# 358MU_IZNWBYTU20260630.net
KiCad netlist of a schematic drawn in Altium Designer
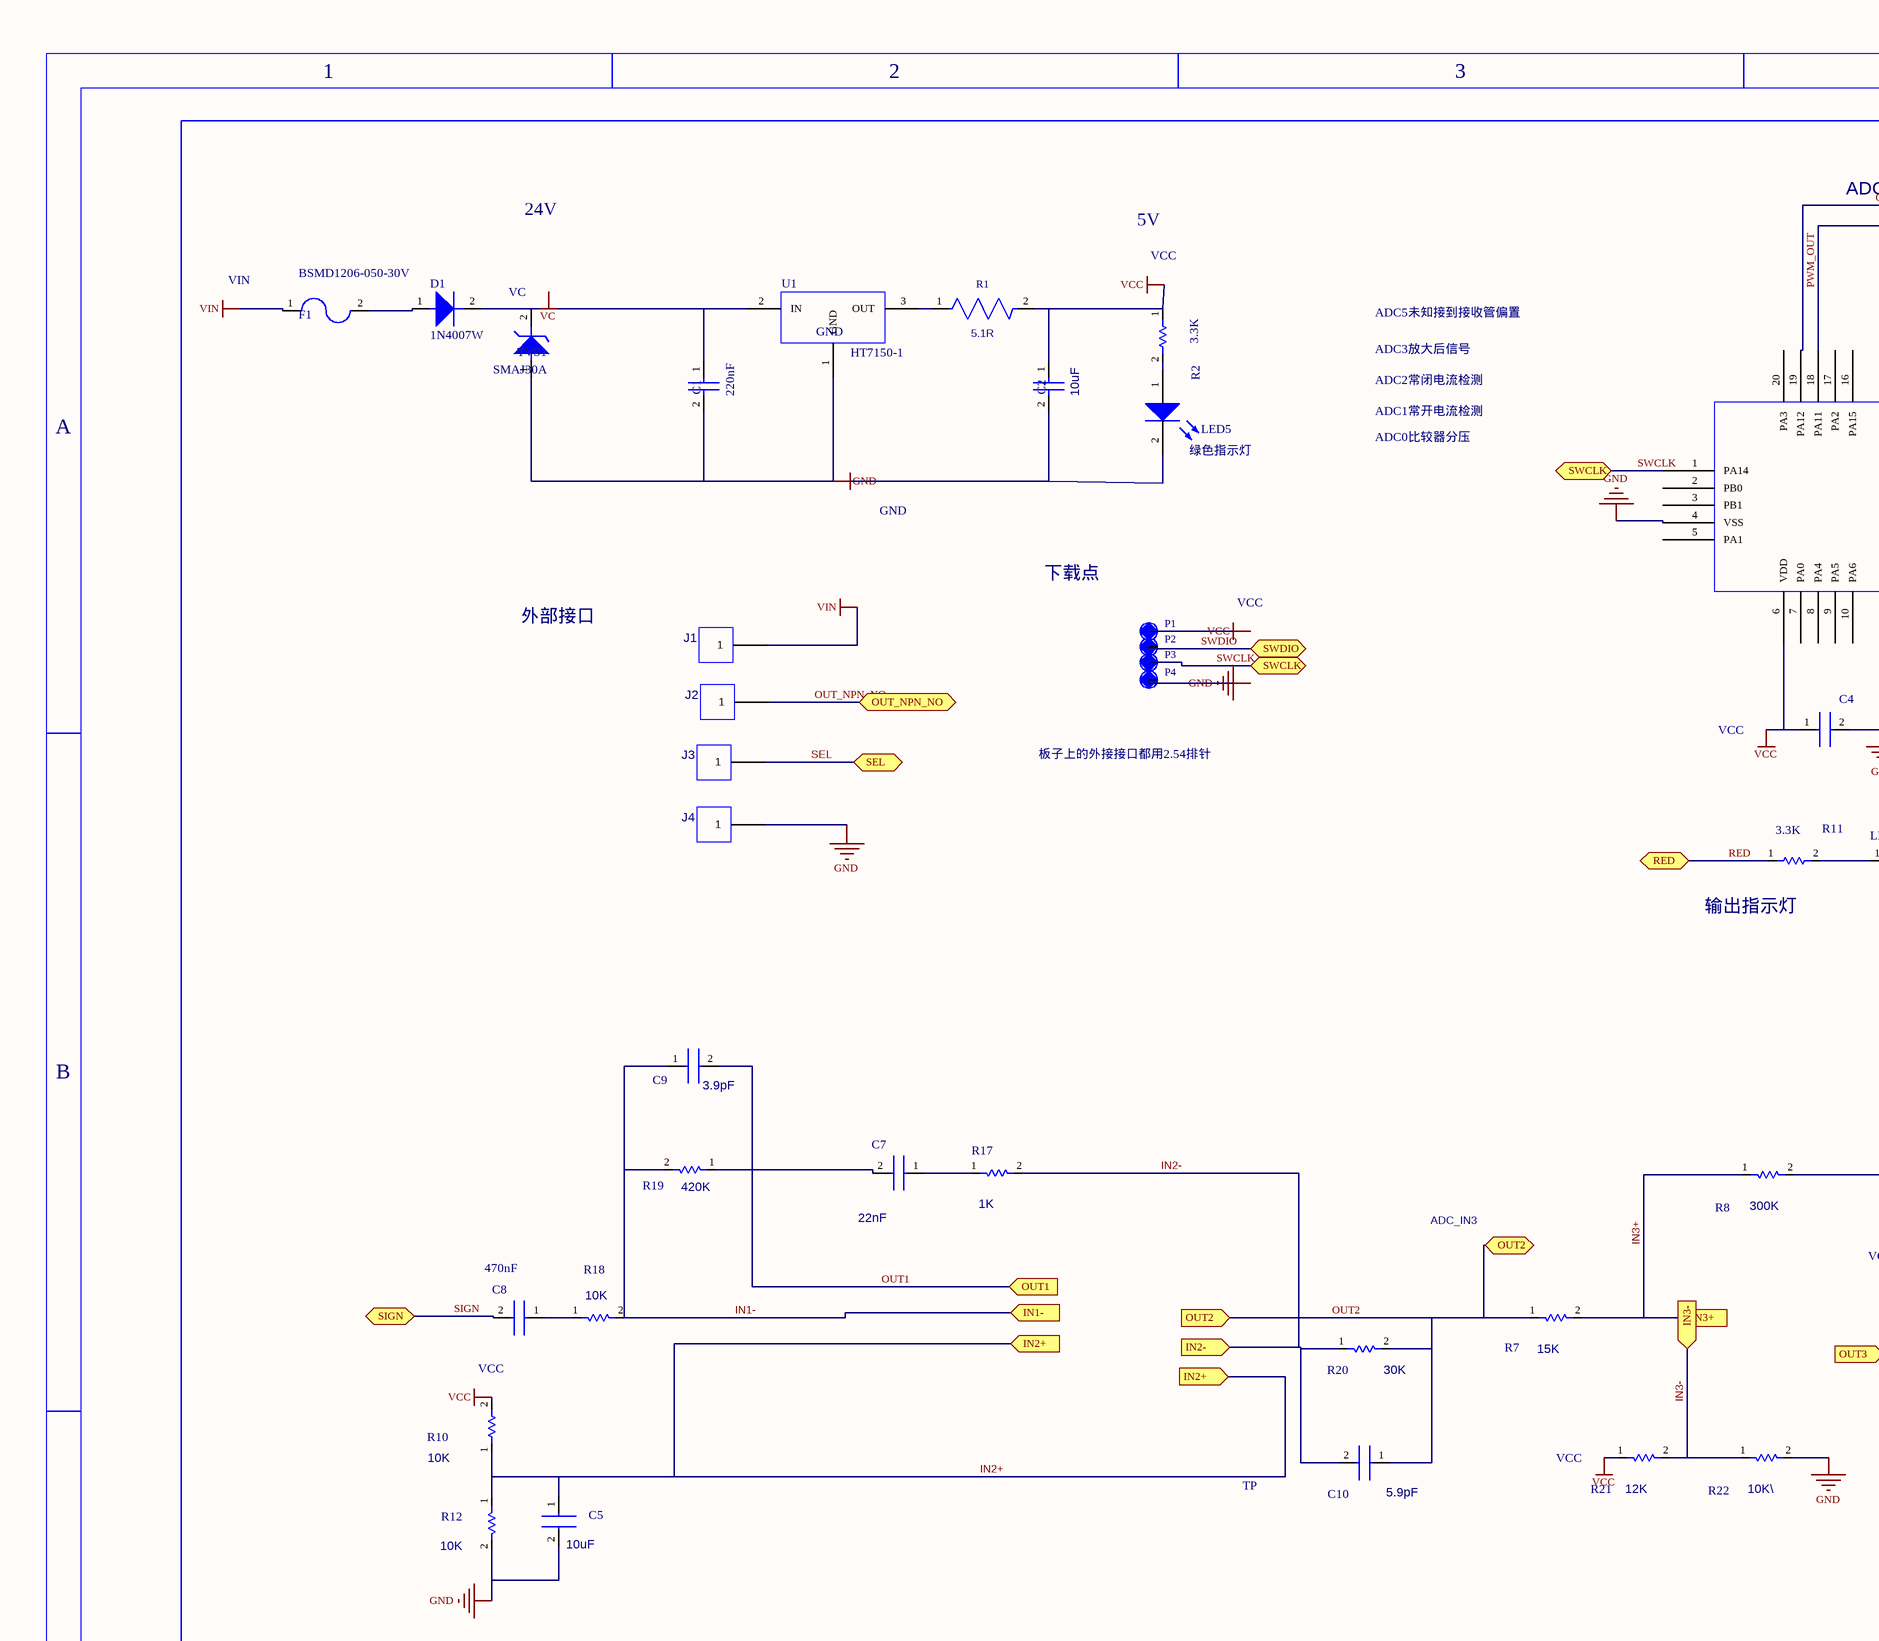
[diagram p0: 358MU&IZNWBYTU20260630.SchDoc, top left]
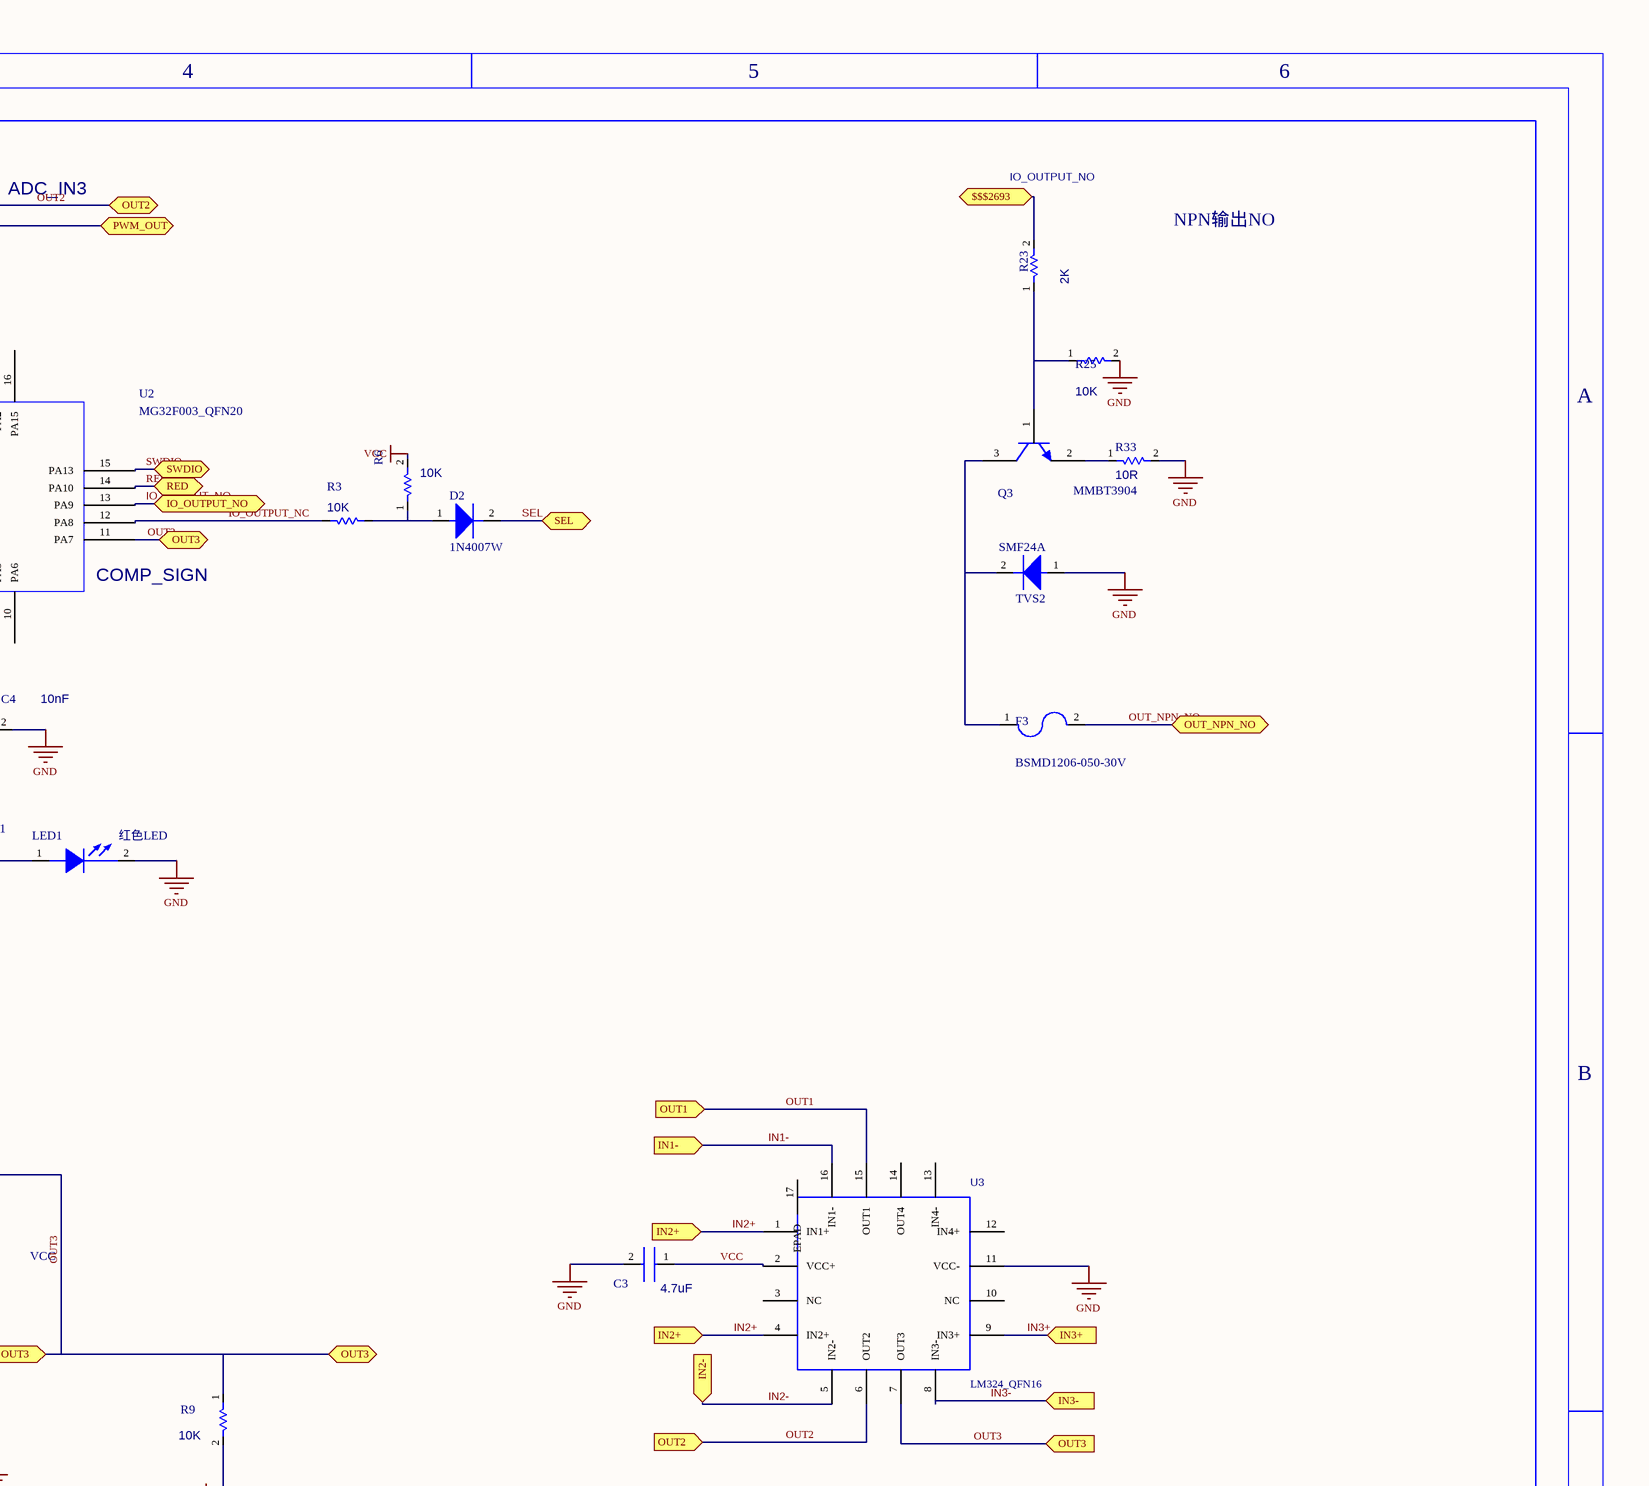
[diagram p1: 358MU&IZNWBYTU20260630.SchDoc, top right]
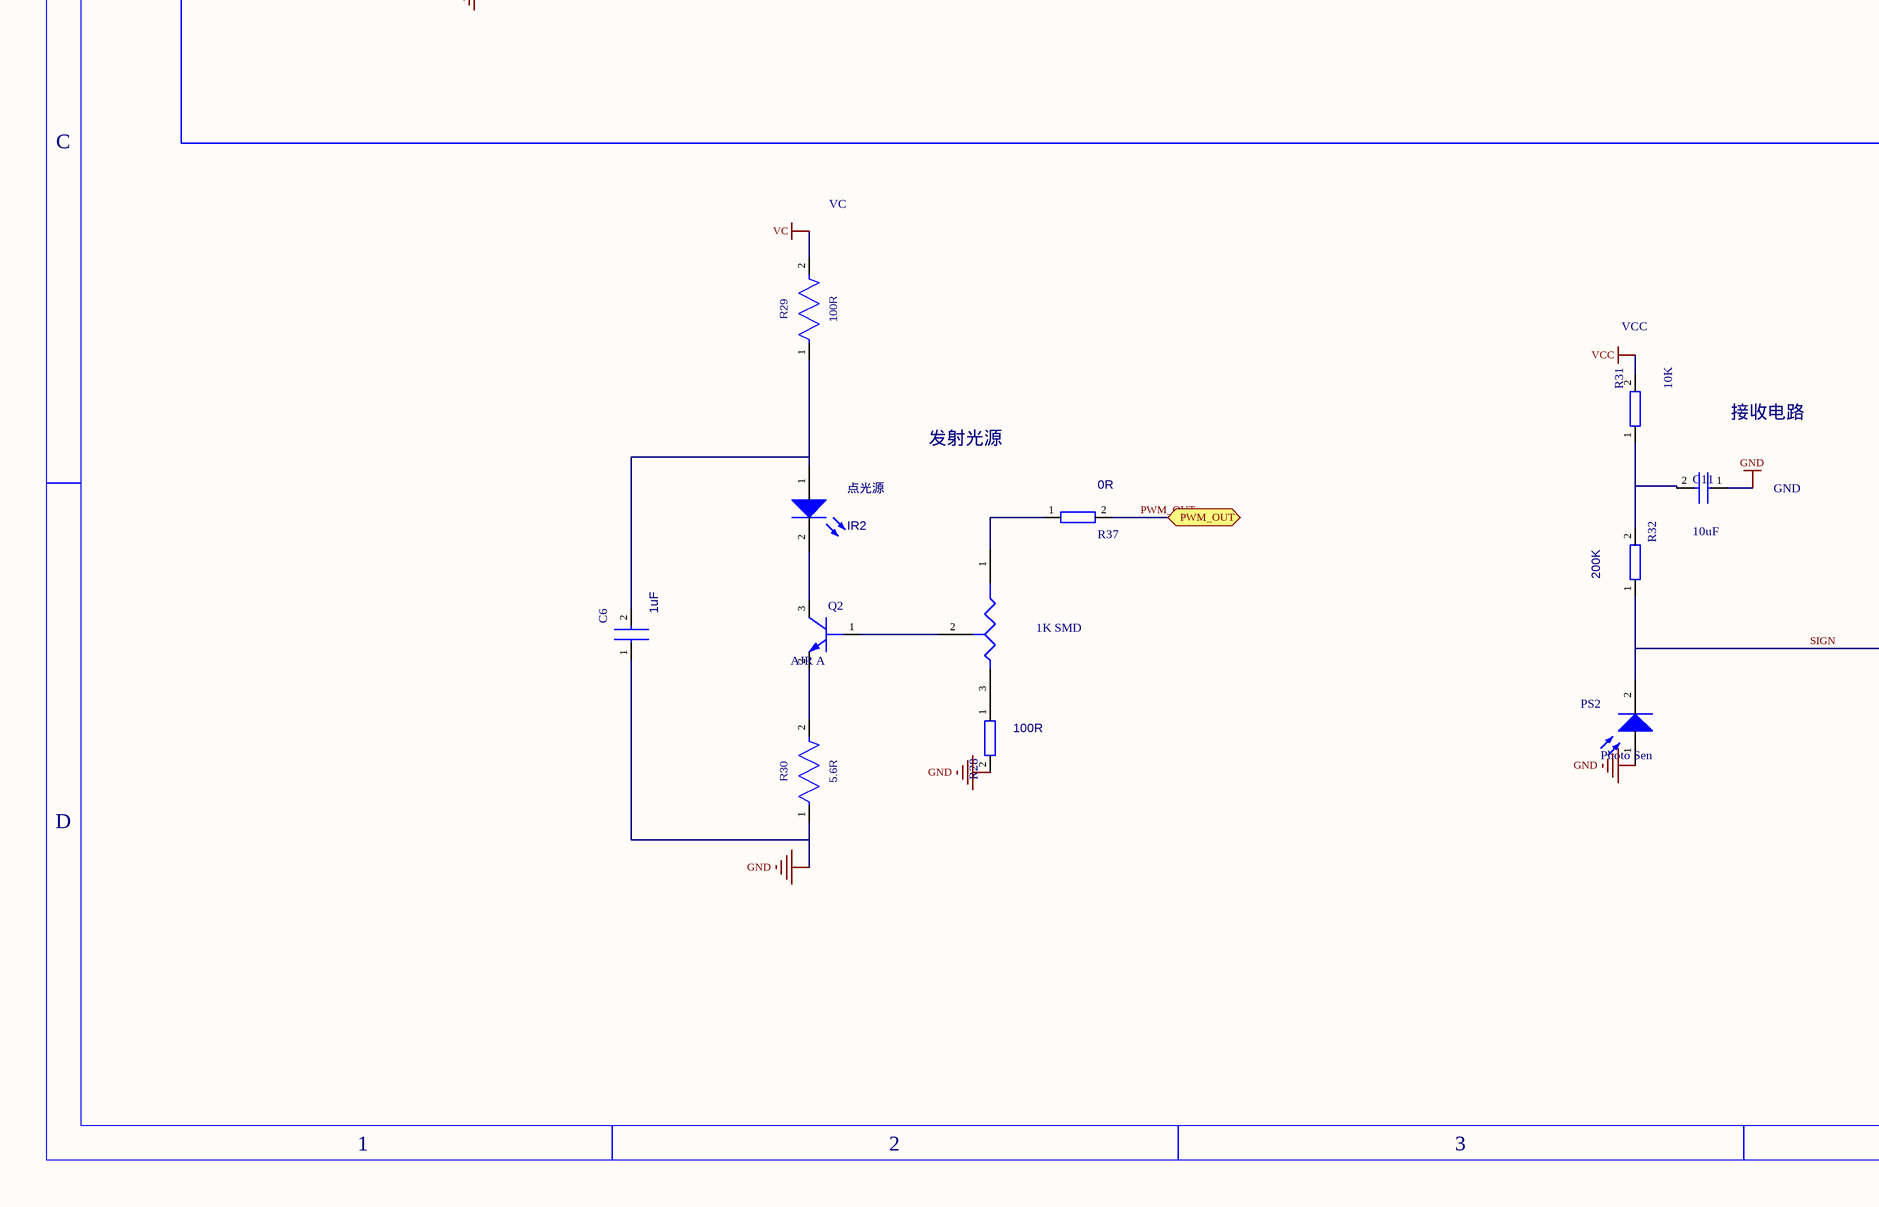
[diagram p2: 358MU&IZNWBYTU20260630.SchDoc, bottom left]
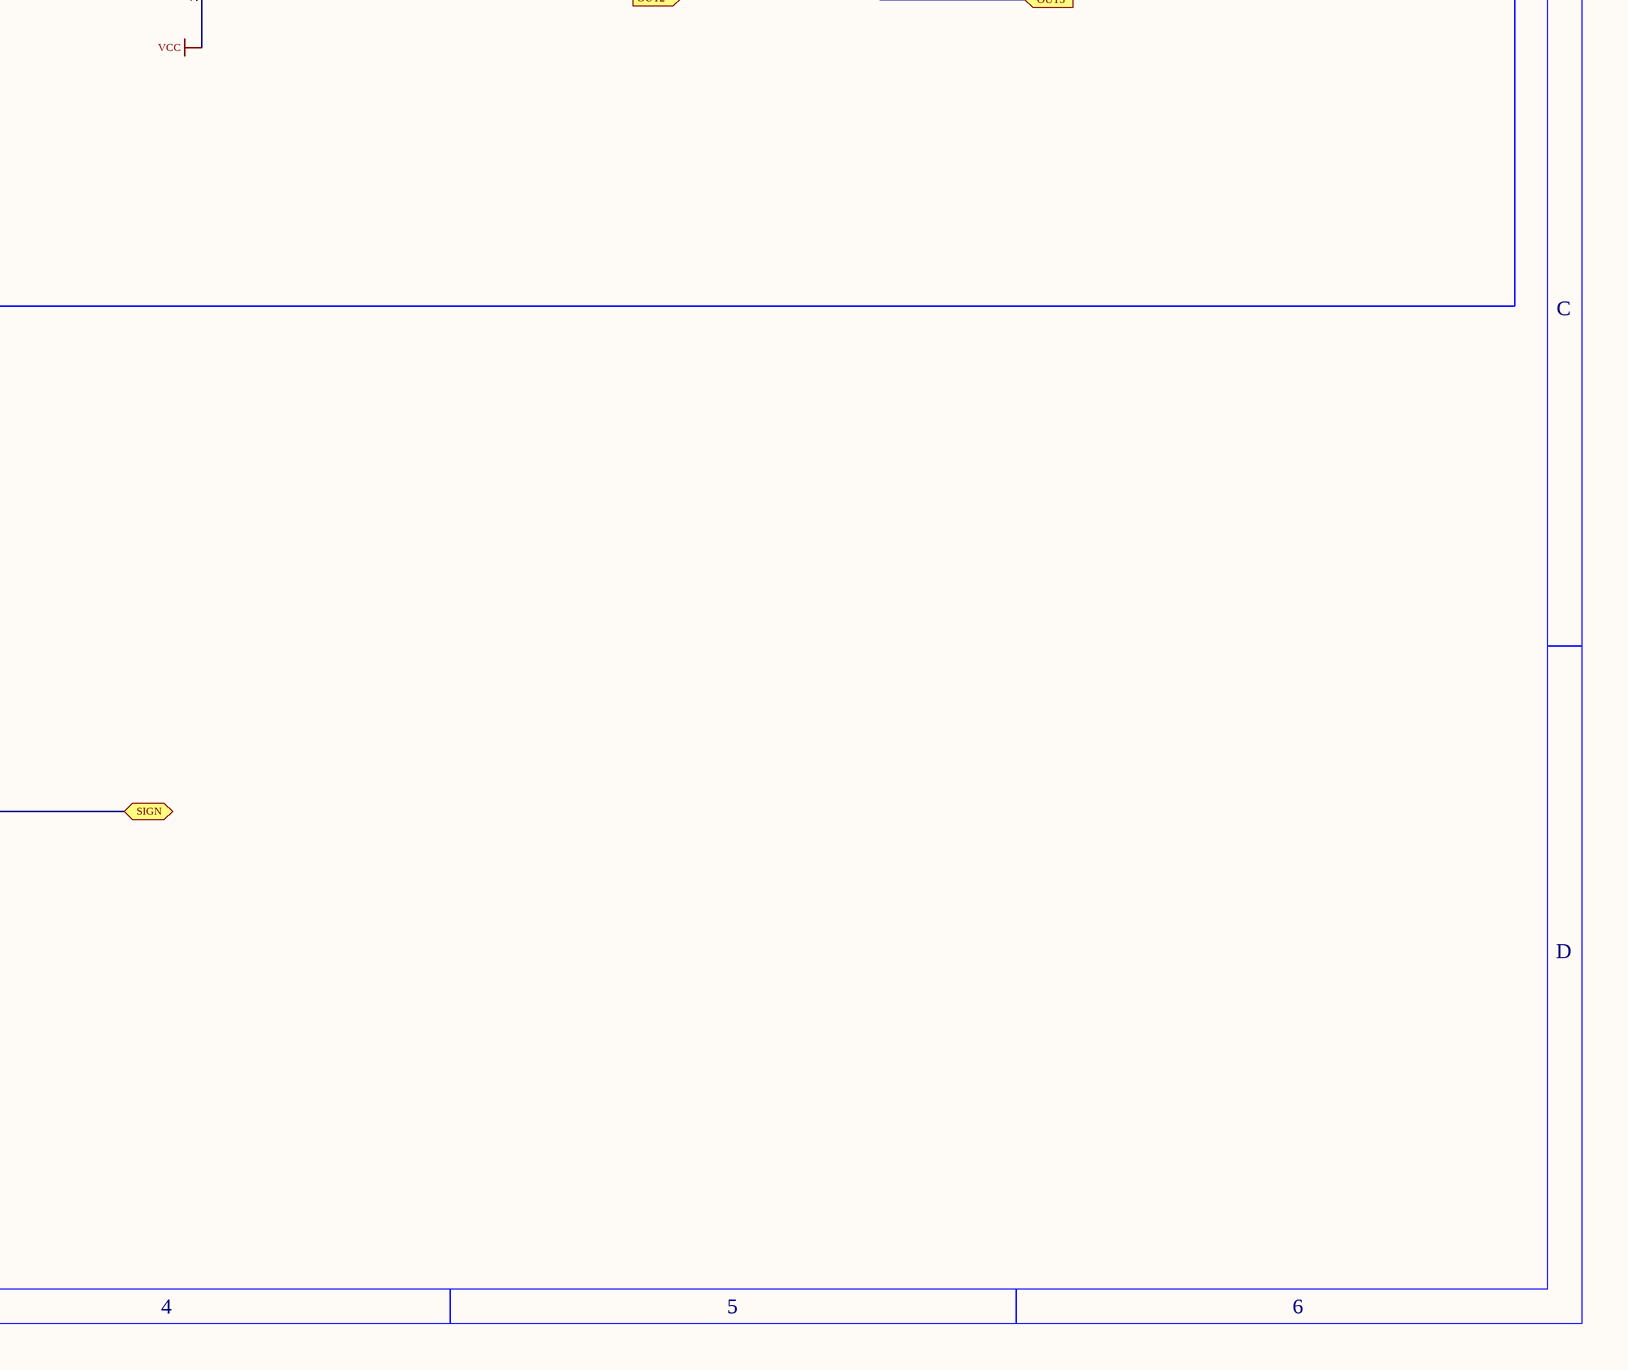
[diagram p3: 358MU&IZNWBYTU20260630.SchDoc, bottom right]

(export (version "E")
  (design (tool "Eeschema 10.0.6"))
  (components
    (comp (ref "C1")
      (value "CAP")
      (footprint "C0603")
      (description "陶瓷电容")
      (libsource (lib "*") (part "CAP"))
    )
    (comp (ref "C2")
      (value "CAP")
      (footprint "C0603")
      (description "陶瓷电容")
      (libsource (lib "*") (part "CAP"))
    )
    (comp (ref "C3") (value "CAP_2") (footprint "C0603") (libsource (lib "*") (part "CAP_2")))
    (comp (ref "C4")
      (value "CAP0402")
      (footprint "CC0402")
      (description "Capacitor")
      (libsource (lib "*") (part "CAP0402"))
    )
    (comp (ref "C5") (value "CAP_2") (footprint "C0603") (libsource (lib "*") (part "CAP_2")))
    (comp (ref "C6")
      (value "CAP0603")
      (footprint "0603C")
      (description "Capacitor")
      (libsource (lib "*") (part "CAP0603"))
    )
    (comp (ref "C7")
      (value "CAP0402")
      (footprint "CC0402")
      (description "Capacitor")
      (libsource (lib "*") (part "CAP0402"))
    )
    (comp (ref "C8")
      (value "CAP0402")
      (footprint "CC0402")
      (description "Capacitor")
      (libsource (lib "*") (part "CAP0402"))
    )
    (comp (ref "C9")
      (value "CAP0402")
      (footprint "CC0402")
      (description "Capacitor")
      (libsource (lib "*") (part "CAP0402"))
    )
    (comp (ref "C10")
      (value "CAP0402")
      (footprint "CC0402")
      (description "Capacitor")
      (libsource (lib "*") (part "CAP0402"))
    )
    (comp (ref "C11") (value "CAP_NP") (footprint "0603") (libsource (lib "*") (part "CAP_NP")))
    (comp (ref "D1")
      (value "DIODE")
      (footprint "WSOD-323")
      (description "Diode")
      (libsource (lib "*") (part "DIODE"))
    )
    (comp (ref "D2")
      (value "DIODE")
      (footprint "WSOD-323")
      (description "Diode")
      (libsource (lib "*") (part "DIODE"))
    )
    (comp (ref "F1")
      (value "FUSE")
      (footprint "0603")
      (description "Fuse")
      (libsource (lib "") (part "FUSE_1"))
    )
    (comp (ref "F3")
      (value "FUSE")
      (footprint "0603")
      (description "Fuse")
      (libsource (lib "*") (part "FUSE"))
    )
    (comp (ref "IR2")
      (value "LED0")
      (footprint "TXLED_SMD")
      (description "Typical INFRARED GaAs LED")
      (fields (field (name "PUBLISHER") "Altium Limited"))
      (libsource (lib "*") (part "LED0"))
    )
    (comp (ref "J1")
      (value "FPAD_3C")
      (footprint "FPAD_3C")
      (description "Connector")
      (libsource (lib "*") (part "FPAD_3C"))
    )
    (comp (ref "J2")
      (value "FPAD_3C")
      (footprint "FPAD_3C")
      (description "Connector")
      (libsource (lib "*") (part "FPAD_3C"))
    )
    (comp (ref "J3")
      (value "FPAD_3C")
      (footprint "FPAD_3C")
      (description "Connector")
      (libsource (lib "*") (part "FPAD_3C"))
    )
    (comp (ref "J4")
      (value "FPAD_3C")
      (footprint "FPAD_3C")
      (description "Connector")
      (libsource (lib "*") (part "FPAD_3C"))
    )
    (comp (ref "LED1") (value "LED") (footprint "LED0603") (libsource (lib "*") (part "LED")))
    (comp (ref "LED5")
      (value "LED2")
      (footprint "LED0603")
      (description "Typical RED, GREEN, YELLOW, AMBER GaAs LED")
      (fields (field (name "PUBLISHER") "Altium Limited"))
      (libsource (lib "*") (part "LED2"))
    )
    (comp (ref "P1")
      (value "TEST_POINTB+")
      (footprint "TEST-POINT_D1.0")
      (libsource (lib "*") (part "TEST_POINTB+"))
    )
    (comp (ref "P2")
      (value "TEST_POINTB+")
      (footprint "TEST-POINT_D1.0")
      (libsource (lib "*") (part "TEST_POINTB+"))
    )
    (comp (ref "P3")
      (value "TEST_POINTB+")
      (footprint "TEST-POINT_D1.0")
      (libsource (lib "*") (part "TEST_POINTB+"))
    )
    (comp (ref "P4")
      (value "TEST_POINTB+")
      (footprint "TEST-POINT_D1.0")
      (libsource (lib "*") (part "TEST_POINTB+"))
    )
    (comp (ref "PS2")
      (value "PHOTO_SEN")
      (footprint "RXLED_SMD")
      (description "Photosensitive Diode")
      (fields (field (name "PUBLISHER") "Altium Limited"))
      (libsource (lib "*") (part "PHOTO_SEN"))
    )
    (comp (ref "Q2") (value "Q2N2369_0") (footprint "SOT23/2") (libsource (lib "*") (part "Q2N2369_0")))
    (comp (ref "Q3")
      (value "NPNSOT23")
      (footprint "SOT23/2")
      (description "NPN Bipolar Transistor")
      (fields (field (name "PUBLISHER") "Altium Limited"))
      (libsource (lib "*") (part "NPNSOT23"))
    )
    (comp (ref "R1")
      (value "5.1R")
      (footprint "0603")
      (description "SURFACE MOUNT RESISTOR 0.031 X 0.061 INCHES, 1/10W")
      (fields (field (name "Comment") "RES0603"))
      (libsource (lib "*") (part "RES0603"))
    )
    (comp (ref "R2") (value "RAS0402") (footprint "R0402") (libsource (lib "*") (part "RAS0402")))
    (comp (ref "R3") (value "RAS0402") (footprint "R0402") (libsource (lib "") (part "RAS0402_1")))
    (comp (ref "R5")
      (value "1K SMD")
      (footprint "SMD")
      (description "Tapped Resistor")
      (fields (field (name "Comment") "ADJ_SMD") (field (name "PUBLISHER") "Altium Limited"))
      (libsource (lib "*") (part "ADJ_SMD"))
    )
    (comp (ref "R6") (value "RAS0402") (footprint "R0402") (libsource (lib "*") (part "RAS0402")))
    (comp (ref "R7") (value "RAS0402") (footprint "R0402") (libsource (lib "*") (part "RAS0402")))
    (comp (ref "R8") (value "RAS0402") (footprint "R0402") (libsource (lib "*") (part "RAS0402")))
    (comp (ref "R9") (value "RAS0402") (footprint "R0402") (libsource (lib "*") (part "RAS0402")))
    (comp (ref "R10") (value "RAS0402") (footprint "R0402") (libsource (lib "*") (part "RAS0402")))
    (comp (ref "R11") (value "RAS0402") (footprint "R0402") (libsource (lib "*") (part "RAS0402")))
    (comp (ref "R12") (value "RAS0402") (footprint "R0402") (libsource (lib "*") (part "RAS0402")))
    (comp (ref "R17") (value "RAS0402") (footprint "R0402") (libsource (lib "*") (part "RAS0402")))
    (comp (ref "R18") (value "RAS0402") (footprint "R0402") (libsource (lib "*") (part "RAS0402")))
    (comp (ref "R19") (value "RAS0402") (footprint "R0402") (libsource (lib "*") (part "RAS0402")))
    (comp (ref "R20") (value "RAS0402") (footprint "R0402") (libsource (lib "*") (part "RAS0402")))
    (comp (ref "R21") (value "RAS0402") (footprint "R0402") (libsource (lib "*") (part "RAS0402")))
    (comp (ref "R22") (value "RAS0402") (footprint "R0402") (libsource (lib "*") (part "RAS0402")))
    (comp (ref "R23") (value "RAS0402") (footprint "R0402") (libsource (lib "*") (part "RAS0402")))
    (comp (ref "R25") (value "RAS0402") (footprint "R0402") (libsource (lib "*") (part "RAS0402")))
    (comp (ref "R28") (value "RES") (footprint "R0603") (libsource (lib "*") (part "RES")))
    (comp (ref "R29")
      (value "100R")
      (footprint "0603")
      (description "SURFACE MOUNT RESISTOR 0.031 X 0.061 INCHES, 1/10W")
      (fields (field (name "Comment") "RES0603"))
      (libsource (lib "*") (part "RES0603"))
    )
    (comp (ref "R30")
      (value "5.6R")
      (footprint "0603")
      (description "SURFACE MOUNT RESISTOR 0.031 X 0.061 INCHES, 1/10W")
      (fields (field (name "Comment") "RES0603"))
      (libsource (lib "*") (part "RES0603"))
    )
    (comp (ref "R31") (value "R0402") (footprint "RES0402") (libsource (lib "*") (part "R0402")))
    (comp (ref "R32") (value "R0402") (footprint "RES0402") (libsource (lib "*") (part "R0402")))
    (comp (ref "R33") (value "RAS") (footprint "0603") (libsource (lib "*") (part "RAS")))
    (comp (ref "R37") (value "R0402") (footprint "RES0402") (libsource (lib "*") (part "R0402")))
    (comp (ref "TVS1")
      (value "DIODE_V")
      (footprint "SOD_523")
      (description "Varactor Diode")
      (libsource (lib "*") (part "DIODE_V"))
    )
    (comp (ref "TVS2")
      (value "SOD523")
      (footprint "SOD_523")
      (description "Diode")
      (fields (field (name "PUBLISHER") "Altium Limited"))
      (libsource (lib "*") (part "SOD523"))
    )
    (comp (ref "U1")
      (value "HT7530-1")
      (footprint "SOT89")
      (description "3.0V 100mA Low Power,  Low Dropout Voltage (LDO) Regulator")
      (fields (field (name "PUBLISHER") "Altium Limited"))
      (libsource (lib "*") (part "HT7530-1"))
    )
    (comp (ref "U2")
      (value "MG32F003-QFN20")
      (footprint "MG32F003_QFN20")
      (description "QFN20主控芯片")
      (libsource (lib "*") (part "MG32F003-QFN20"))
    )
    (comp (ref "U3")
      (value "LM324_QFN16")
      (footprint "LM324_QFN16")
      (libsource (lib "*") (part "LM324_QFN16"))
    )
  )
  (nets
    (net (code "1") (name "/$$$2693") (class "Default")
      (node (ref "R23") (pin "2") (pinfunction "2_2") (pintype "passive"))
    )
    (net (code "2") (name "/IN1-") (class "Default")
      (node (ref "C9") (pin "1") (pinfunction "1_1") (pintype "passive"))
      (node (ref "R18") (pin "2") (pinfunction "2_2") (pintype "passive"))
      (node (ref "R19") (pin "2") (pinfunction "2_2") (pintype "passive"))
      (node (ref "U3") (pin "16") (pinfunction "IN1-_16") (pintype "passive"))
    )
    (net (code "3") (name "/IN2+") (class "Default")
      (node (ref "C5") (pin "1") (pinfunction "1_1") (pintype "passive"))
      (node (ref "R10") (pin "1") (pinfunction "1_1") (pintype "passive"))
      (node (ref "R12") (pin "1") (pinfunction "1_1") (pintype "passive"))
      (node (ref "U3") (pin "1") (pinfunction "IN1+_1") (pintype "passive"))
      (node (ref "U3") (pin "4") (pinfunction "IN2+_4") (pintype "passive"))
    )
    (net (code "4") (name "/IN2-") (class "Default")
      (node (ref "C10") (pin "2") (pinfunction "2_2") (pintype "passive"))
      (node (ref "R17") (pin "2") (pinfunction "2_2") (pintype "passive"))
      (node (ref "R20") (pin "1") (pinfunction "1_1") (pintype "passive"))
      (node (ref "U3") (pin "5") (pinfunction "IN2-_5") (pintype "passive"))
    )
    (net (code "5") (name "/IN3+") (class "Default")
      (node (ref "R7") (pin "2") (pinfunction "2_2") (pintype "passive"))
      (node (ref "R8") (pin "1") (pinfunction "1_1") (pintype "passive"))
      (node (ref "U3") (pin "9") (pinfunction "IN3+_9") (pintype "passive"))
    )
    (net (code "6") (name "/IN3-") (class "Default")
      (node (ref "R21") (pin "2") (pinfunction "2_2") (pintype "passive"))
      (node (ref "R22") (pin "1") (pinfunction "1_1") (pintype "passive"))
      (node (ref "U3") (pin "8") (pinfunction "IN3-_8") (pintype "passive"))
    )
    (net (code "7") (name "/IO_OUTPUT_NC") (class "Default")
      (node (ref "R3") (pin "1") (pinfunction "1_1") (pintype "passive"))
      (node (ref "U2") (pin "12") (pinfunction "PA8_12") (pintype "passive"))
    )
    (net (code "8") (name "/IO_OUTPUT_NO") (class "Default")
      (node (ref "U2") (pin "13") (pinfunction "PA9_13") (pintype "passive"))
    )
    (net (code "9") (name "/OUT1") (class "Default")
      (node (ref "C7") (pin "2") (pinfunction "2_2") (pintype "passive"))
      (node (ref "C9") (pin "2") (pinfunction "2_2") (pintype "passive"))
      (node (ref "R19") (pin "1") (pinfunction "1_1") (pintype "passive"))
      (node (ref "U3") (pin "15") (pinfunction "OUT1_15") (pintype "passive"))
    )
    (net (code "10") (name "/OUT2") (class "Default")
      (node (ref "C10") (pin "1") (pinfunction "1_1") (pintype "passive"))
      (node (ref "R20") (pin "2") (pinfunction "2_2") (pintype "passive"))
      (node (ref "R7") (pin "1") (pinfunction "1_1") (pintype "passive"))
      (node (ref "U2") (pin "19") (pinfunction "PA12_19") (pintype "passive"))
      (node (ref "U3") (pin "6") (pinfunction "OUT2_6") (pintype "passive"))
    )
    (net (code "11") (name "/OUT3") (class "Default")
      (node (ref "R8") (pin "2") (pinfunction "2_2") (pintype "passive"))
      (node (ref "R9") (pin "1") (pinfunction "1_1") (pintype "passive"))
      (node (ref "U2") (pin "11") (pinfunction "PA7_11") (pintype "passive"))
      (node (ref "U3") (pin "7") (pinfunction "OUT3_7") (pintype "passive"))
    )
    (net (code "12") (name "/OUT_NPN_NO") (class "Default")
      (node (ref "F3") (pin "2") (pinfunction "2_2") (pintype "passive"))
      (node (ref "J2") (pin "1") (pinfunction "1_1") (pintype "passive"))
    )
    (net (code "13") (name "/PWM_OUT") (class "Default")
      (node (ref "R37") (pin "2") (pinfunction "2_2") (pintype "passive"))
      (node (ref "U2") (pin "18") (pinfunction "PA11_18") (pintype "passive"))
    )
    (net (code "14") (name "/RED") (class "Default")
      (node (ref "R11") (pin "1") (pinfunction "1_1") (pintype "passive"))
      (node (ref "U2") (pin "14") (pinfunction "PA10_14") (pintype "passive"))
    )
    (net (code "15") (name "/SEL") (class "Default")
      (node (ref "D2") (pin "2") (pinfunction "K_2") (pintype "passive"))
      (node (ref "J3") (pin "1") (pinfunction "1_1") (pintype "passive"))
    )
    (net (code "16") (name "/SIGN") (class "Default")
      (node (ref "C8") (pin "2") (pinfunction "2_2") (pintype "passive"))
      (node (ref "PS2") (pin "2") (pinfunction "K_2") (pintype "passive"))
      (node (ref "R32") (pin "1") (pinfunction "1_1") (pintype "passive"))
    )
    (net (code "17") (name "/SWCLK") (class "Default")
      (node (ref "P3") (pin "1") (pinfunction "1_1") (pintype "passive"))
      (node (ref "U2") (pin "1") (pinfunction "PA14_1") (pintype "passive"))
    )
    (net (code "18") (name "/SWDIO") (class "Default")
      (node (ref "P2") (pin "1") (pinfunction "1_1") (pintype "passive"))
      (node (ref "U2") (pin "15") (pinfunction "PA13_15") (pintype "passive"))
    )
    (net (code "19") (name "GND") (class "Default")
      (node (ref "C1") (pin "2") (pinfunction "2_2") (pintype "passive"))
      (node (ref "C11") (pin "1") (pinfunction "1_1") (pintype "passive"))
      (node (ref "C2") (pin "2") (pinfunction "2_2") (pintype "passive"))
      (node (ref "C3") (pin "2") (pinfunction "2_2") (pintype "passive"))
      (node (ref "C4") (pin "2") (pinfunction "2_2") (pintype "passive"))
      (node (ref "C5") (pin "2") (pinfunction "2_2") (pintype "passive"))
      (node (ref "C6") (pin "1") (pinfunction "1_1") (pintype "passive"))
      (node (ref "J4") (pin "1") (pinfunction "1_1") (pintype "passive"))
      (node (ref "LED1") (pin "2") (pinfunction "CATHODE_2") (pintype "passive"))
      (node (ref "LED5") (pin "2") (pinfunction "K_2") (pintype "passive"))
      (node (ref "P4") (pin "1") (pinfunction "1_1") (pintype "passive"))
      (node (ref "PS2") (pin "1") (pinfunction "A_1") (pintype "passive"))
      (node (ref "R12") (pin "2") (pinfunction "2_2") (pintype "passive"))
      (node (ref "R22") (pin "2") (pinfunction "2_2") (pintype "passive"))
      (node (ref "R25") (pin "2") (pinfunction "2_2") (pintype "passive"))
      (node (ref "R28") (pin "2") (pinfunction "2_2") (pintype "passive"))
      (node (ref "R30") (pin "1") (pinfunction "1_1") (pintype "passive"))
      (node (ref "R33") (pin "2") (pinfunction "2_2") (pintype "passive"))
      (node (ref "TVS1") (pin "1") (pinfunction "1_1") (pintype "passive"))
      (node (ref "TVS2") (pin "1") (pinfunction "A_1") (pintype "passive"))
      (node (ref "U1") (pin "1") (pinfunction "GND_1") (pintype "power_in"))
      (node (ref "U2") (pin "4") (pinfunction "VSS_4") (pintype "passive"))
      (node (ref "U3") (pin "11") (pinfunction "VCC-_11") (pintype "passive"))
    )
    (net (code "20") (name "Net-(C7-Pad1)") (class "Default")
      (node (ref "C7") (pin "1") (pinfunction "1_1") (pintype "passive"))
      (node (ref "R17") (pin "1") (pinfunction "1_1") (pintype "passive"))
    )
    (net (code "21") (name "Net-(C8-Pad1)") (class "Default")
      (node (ref "C8") (pin "1") (pinfunction "1_1") (pintype "passive"))
      (node (ref "R18") (pin "1") (pinfunction "1_1") (pintype "passive"))
    )
    (net (code "22") (name "Net-(C11-Pad2)") (class "Default")
      (node (ref "C11") (pin "2") (pinfunction "2_2") (pintype "passive"))
      (node (ref "R31") (pin "1") (pinfunction "1_1") (pintype "passive"))
      (node (ref "R32") (pin "2") (pinfunction "2_2") (pintype "passive"))
    )
    (net (code "23") (name "Net-(D1-A)") (class "Default")
      (node (ref "D1") (pin "1") (pinfunction "A_1") (pintype "passive"))
      (node (ref "F1") (pin "2") (pinfunction "2_2") (pintype "passive"))
    )
    (net (code "24") (name "Net-(D2-A)") (class "Default")
      (node (ref "D2") (pin "1") (pinfunction "A_1") (pintype "passive"))
      (node (ref "R3") (pin "2") (pinfunction "2_2") (pintype "passive"))
      (node (ref "R6") (pin "1") (pinfunction "1_1") (pintype "passive"))
    )
    (net (code "25") (name "Net-(IR2-A)") (class "Default")
      (node (ref "C6") (pin "2") (pinfunction "2_2") (pintype "passive"))
      (node (ref "IR2") (pin "1") (pinfunction "A_1") (pintype "passive"))
      (node (ref "R29") (pin "1") (pinfunction "1_1") (pintype "passive"))
    )
    (net (code "26") (name "Net-(IR2-K)") (class "Default")
      (node (ref "IR2") (pin "2") (pinfunction "K_2") (pintype "passive"))
      (node (ref "Q2") (pin "3") (pinfunction "COLLECTOR_3") (pintype "passive"))
    )
    (net (code "27") (name "Net-(LED1-ANODE)") (class "Default")
      (node (ref "LED1") (pin "1") (pinfunction "ANODE_1") (pintype "passive"))
      (node (ref "R11") (pin "2") (pinfunction "2_2") (pintype "passive"))
    )
    (net (code "28") (name "Net-(LED5-A)") (class "Default")
      (node (ref "LED5") (pin "1") (pinfunction "A_1") (pintype "passive"))
      (node (ref "R2") (pin "2") (pinfunction "2_2") (pintype "passive"))
    )
    (net (code "29") (name "Net-(Q2-BASE)") (class "Default")
      (node (ref "Q2") (pin "1") (pinfunction "BASE_1") (pintype "passive"))
      (node (ref "R5") (pin "2") (pinfunction "TAP_2") (pintype "passive"))
    )
    (net (code "30") (name "Net-(Q2-EMITTER)") (class "Default")
      (node (ref "Q2") (pin "2") (pinfunction "EMITTER_2") (pintype "passive"))
      (node (ref "R30") (pin "2") (pinfunction "2_2") (pintype "passive"))
    )
    (net (code "31") (name "Net-(Q3-B)") (class "Default")
      (node (ref "Q3") (pin "1") (pinfunction "B_1") (pintype "passive"))
      (node (ref "R23") (pin "1") (pinfunction "1_1") (pintype "passive"))
      (node (ref "R25") (pin "1") (pinfunction "1_1") (pintype "passive"))
    )
    (net (code "32") (name "Net-(Q3-C)") (class "Default")
      (node (ref "F3") (pin "1") (pinfunction "1_1") (pintype "passive"))
      (node (ref "Q3") (pin "3") (pinfunction "C_3") (pintype "passive"))
      (node (ref "TVS2") (pin "2") (pinfunction "K_2") (pintype "passive"))
    )
    (net (code "33") (name "Net-(Q3-E)") (class "Default")
      (node (ref "Q3") (pin "2") (pinfunction "E_2") (pintype "passive"))
      (node (ref "R33") (pin "1") (pinfunction "1_1") (pintype "passive"))
    )
    (net (code "34") (name "Net-(R5-A)") (class "Default")
      (node (ref "R28") (pin "1") (pinfunction "1_1") (pintype "passive"))
      (node (ref "R5") (pin "3") (pinfunction "A_3") (pintype "passive"))
    )
    (net (code "35") (name "Net-(R5-B)") (class "Default")
      (node (ref "R37") (pin "1") (pinfunction "1_1") (pintype "passive"))
      (node (ref "R5") (pin "1") (pinfunction "B_1") (pintype "passive"))
    )
    (net (code "36") (name "Net-(U1-OUT)") (class "Default")
      (node (ref "R1") (pin "1") (pinfunction "1_1") (pintype "passive"))
      (node (ref "U1") (pin "3") (pinfunction "OUT_3") (pintype "power_in"))
    )
    (net (code "37") (name "VC") (class "Default")
      (node (ref "C1") (pin "1") (pinfunction "1_1") (pintype "passive"))
      (node (ref "D1") (pin "2") (pinfunction "K_2") (pintype "passive"))
      (node (ref "R29") (pin "2") (pinfunction "2_2") (pintype "passive"))
      (node (ref "TVS1") (pin "2") (pinfunction "2_2") (pintype "passive"))
      (node (ref "U1") (pin "2") (pinfunction "IN_2") (pintype "power_in"))
    )
    (net (code "38") (name "VCC") (class "Default")
      (node (ref "C2") (pin "1") (pinfunction "1_1") (pintype "passive"))
      (node (ref "C3") (pin "1") (pinfunction "1_1") (pintype "passive"))
      (node (ref "C4") (pin "1") (pinfunction "1_1") (pintype "passive"))
      (node (ref "P1") (pin "1") (pinfunction "1_1") (pintype "passive"))
      (node (ref "R1") (pin "2") (pinfunction "2_2") (pintype "passive"))
      (node (ref "R10") (pin "2") (pinfunction "2_2") (pintype "passive"))
      (node (ref "R2") (pin "1") (pinfunction "1_1") (pintype "passive"))
      (node (ref "R21") (pin "1") (pinfunction "1_1") (pintype "passive"))
      (node (ref "R31") (pin "2") (pinfunction "2_2") (pintype "passive"))
      (node (ref "R6") (pin "2") (pinfunction "2_2") (pintype "passive"))
      (node (ref "R9") (pin "2") (pinfunction "2_2") (pintype "passive"))
      (node (ref "U2") (pin "6") (pinfunction "VDD_6") (pintype "passive"))
      (node (ref "U3") (pin "2") (pinfunction "VCC+_2") (pintype "passive"))
    )
    (net (code "39") (name "VIN") (class "Default")
      (node (ref "F1") (pin "1") (pinfunction "1_1") (pintype "passive"))
      (node (ref "J1") (pin "1") (pinfunction "1_1") (pintype "passive"))
    )
    (net (code "40") (name "unconnected-(U2-PA0-Pad7)") (class "Default")
      (node (ref "U2") (pin "7") (pinfunction "PA0_7") (pintype "passive"))
    )
    (net (code "41") (name "unconnected-(U2-PA1-Pad5)") (class "Default")
      (node (ref "U2") (pin "5") (pinfunction "PA1_5") (pintype "passive"))
    )
    (net (code "42") (name "unconnected-(U2-PA2-Pad17)") (class "Default")
      (node (ref "U2") (pin "17") (pinfunction "PA2_17") (pintype "passive"))
    )
    (net (code "43") (name "unconnected-(U2-PA3-Pad20)") (class "Default")
      (node (ref "U2") (pin "20") (pinfunction "PA3_20") (pintype "passive"))
    )
    (net (code "44") (name "unconnected-(U2-PA4-Pad8)") (class "Default")
      (node (ref "U2") (pin "8") (pinfunction "PA4_8") (pintype "passive"))
    )
    (net (code "45") (name "unconnected-(U2-PA5-Pad9)") (class "Default")
      (node (ref "U2") (pin "9") (pinfunction "PA5_9") (pintype "passive"))
    )
    (net (code "46") (name "unconnected-(U2-PA6-Pad10)") (class "Default")
      (node (ref "U2") (pin "10") (pinfunction "PA6_10") (pintype "passive"))
    )
    (net (code "47") (name "unconnected-(U2-PA15-Pad16)") (class "Default")
      (node (ref "U2") (pin "16") (pinfunction "PA15_16") (pintype "passive"))
    )
    (net (code "48") (name "unconnected-(U2-PB0-Pad2)") (class "Default")
      (node (ref "U2") (pin "2") (pinfunction "PB0_2") (pintype "passive"))
    )
    (net (code "49") (name "unconnected-(U2-PB1-Pad3)") (class "Default")
      (node (ref "U2") (pin "3") (pinfunction "PB1_3") (pintype "passive"))
    )
    (net (code "50") (name "unconnected-(U3-EPAD-Pad17)") (class "Default")
      (node (ref "U3") (pin "17") (pinfunction "EPAD_17") (pintype "passive"))
    )
    (net (code "51") (name "unconnected-(U3-IN4+-Pad12)") (class "Default")
      (node (ref "U3") (pin "12") (pinfunction "IN4+_12") (pintype "passive"))
    )
    (net (code "52") (name "unconnected-(U3-IN4--Pad13)") (class "Default")
      (node (ref "U3") (pin "13") (pinfunction "IN4-_13") (pintype "passive"))
    )
    (net (code "53") (name "unconnected-(U3-NC-Pad3)") (class "Default")
      (node (ref "U3") (pin "3") (pinfunction "NC_3") (pintype "passive"))
    )
    (net (code "54") (name "unconnected-(U3-NC-Pad10)") (class "Default")
      (node (ref "U3") (pin "10") (pinfunction "NC_10") (pintype "passive"))
    )
    (net (code "55") (name "unconnected-(U3-OUT4-Pad14)") (class "Default")
      (node (ref "U3") (pin "14") (pinfunction "OUT4_14") (pintype "passive"))
    )
  )
)
